# EnvironmentMonitorV2.net
KiCad netlist of a schematic drawn in EAGLE
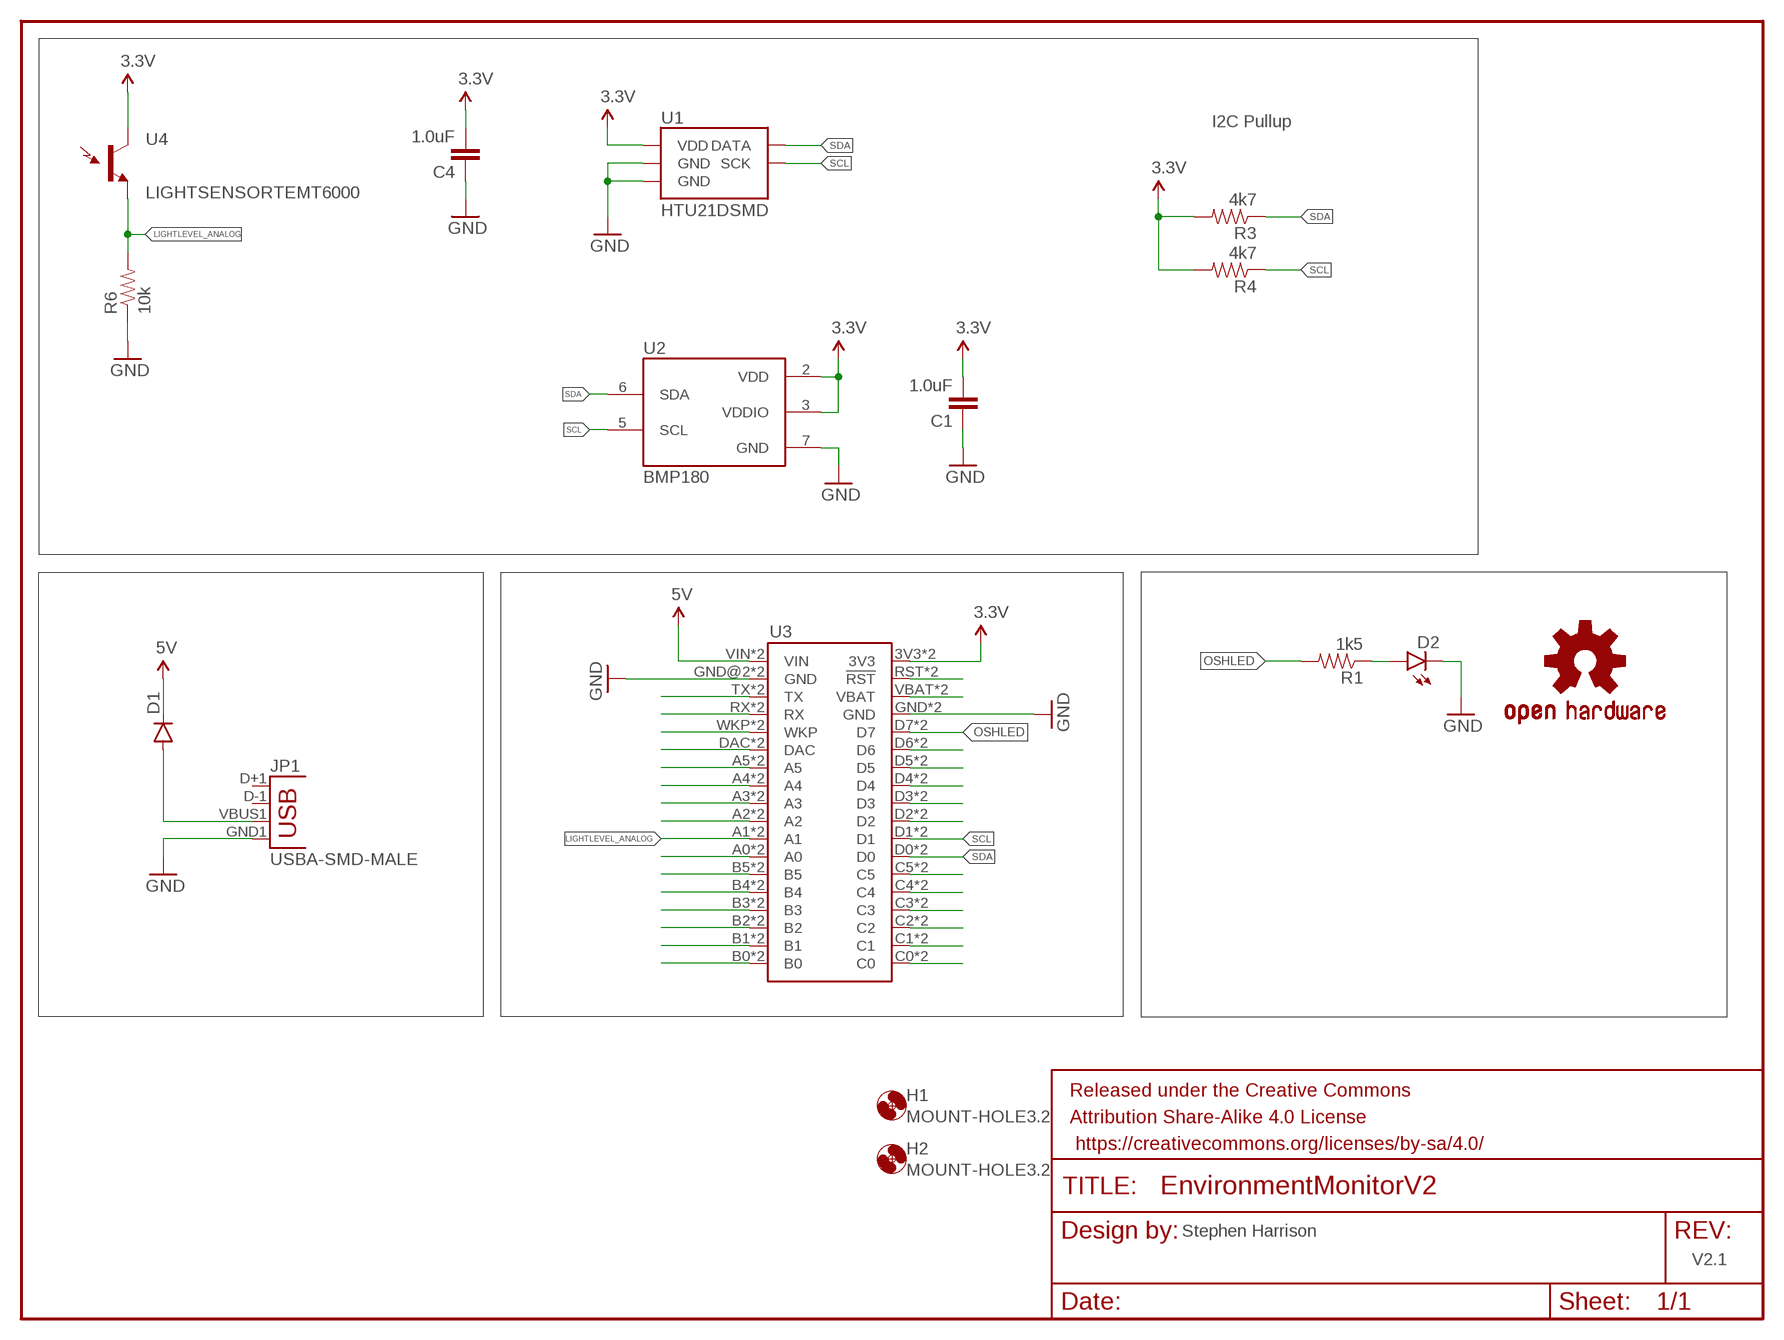
[diagram p0: schematic, sheet 1]

(export (version "E")
  (design (tool "Eeschema 10.0.6"))
  (components
    (comp (ref "C1")
      (value "1.0uF")
      (footprint "eagle-import:0805-CAP")
      (libsource (lib "eagle-import") (part "1.0UF-25V-+80/-20(0805){dblquote}"))
    )
    (comp (ref "C4")
      (value "1.0uF")
      (footprint "eagle-import:0805-CAP")
      (libsource (lib "eagle-import") (part "1.0UF-25V-+80/-20(0805){dblquote}"))
    )
    (comp (ref "D1")
      (value "DIODESMA")
      (footprint "eagle-import:SMA-DIODE")
      (libsource (lib "eagle-import") (part "DIODESMA"))
    )
    (comp (ref "D2")
      (value "LED1206-BOTTOM")
      (footprint "eagle-import:LED-1206-BOTTOM")
      (libsource (lib "eagle-import") (part "LED1206-BOTTOM"))
    )
    (comp (ref "FRAME1")
      (value "FRAME-LETTER")
      (footprint "eagle-import:CREATIVE_COMMONS")
      (libsource (lib "eagle-import") (part "FRAME-LETTER"))
    )
    (comp (ref "H1")
      (value "MOUNT-HOLE3.2")
      (footprint "eagle-import:3,2")
      (libsource (lib "eagle-import") (part "MOUNT-HOLE3.2"))
    )
    (comp (ref "H2")
      (value "MOUNT-HOLE3.2")
      (footprint "eagle-import:3,2")
      (libsource (lib "eagle-import") (part "MOUNT-HOLE3.2"))
    )
    (comp (ref "JP1")
      (value "USBA-SMD-MALE")
      (footprint "eagle-import:USB-A-SMT-MALE")
      (libsource (lib "eagle-import") (part "USBA-SMD-MALE"))
    )
    (comp (ref "LOGO1")
      (value "OSHW-LOGOM")
      (footprint "eagle-import:OSHW-LOGO-M")
      (libsource (lib "eagle-import") (part "OSHW-LOGOM"))
    )
    (comp (ref "R1")
      (value "1k5")
      (footprint "eagle-import:0805")
      (libsource (lib "eagle-import") (part "RESISTOR0805-RES"))
    )
    (comp (ref "R3")
      (value "4k7")
      (footprint "eagle-import:0805")
      (libsource (lib "eagle-import") (part "RESISTOR0805-RES"))
    )
    (comp (ref "R4")
      (value "4k7")
      (footprint "eagle-import:0805")
      (libsource (lib "eagle-import") (part "RESISTOR0805-RES"))
    )
    (comp (ref "R6")
      (value "10k")
      (footprint "eagle-import:0805")
      (libsource (lib "eagle-import") (part "RESISTOR0805-RES"))
    )
    (comp (ref "U1")
      (value "HTU21DSMD")
      (footprint "eagle-import:HTU21D")
      (libsource (lib "eagle-import") (part "HTU21DSMD"))
    )
    (comp (ref "U2")
      (value "BMP180")
      (footprint "eagle-import:BMP180")
      (libsource (lib "eagle-import") (part "BMP180"))
    )
    (comp (ref "U3")
      (value "ELECTRONDUALNAMED")
      (footprint "eagle-import:ELECTRON_SIMPLE_SILK_NAMES_DUAL")
      (libsource (lib "eagle-import") (part "ELECTRONDUALNAMED"))
    )
    (comp (ref "U4")
      (value "LIGHTSENSORTEMT6000")
      (footprint "eagle-import:TEMT6000-SEN")
      (libsource (lib "eagle-import") (part "LIGHTSENSORTEMT6000"))
    )
  )
  (nets
    (net (code "1") (name "3.3V") (class "Default")
      (node (ref "C1") (pin "2") (pinfunction "2_2") (pintype "passive"))
      (node (ref "C4") (pin "2") (pinfunction "2_2") (pintype "passive"))
      (node (ref "R3") (pin "2") (pinfunction "2_2") (pintype "passive"))
      (node (ref "R4") (pin "2") (pinfunction "2_2") (pintype "passive"))
      (node (ref "U1") (pin "VDD") (pinfunction "VDD_VDD") (pintype "power_in"))
      (node (ref "U2") (pin "2") (pinfunction "VDD_2") (pintype "power_in"))
      (node (ref "U2") (pin "3") (pinfunction "VDDIO_3") (pintype "power_in"))
      (node (ref "U3") (pin "3V3") (pinfunction "3V3_3V3") (pintype "power_in"))
      (node (ref "U3") (pin "3V3_1") (pinfunction "3V3_3V3_1") (pintype "power_in"))
      (node (ref "U4") (pin "COLLECTOR") (pinfunction "C1_COLLECTOR") (pintype "passive"))
    )
    (net (code "2") (name "5V") (class "Default")
      (node (ref "D1") (pin "C") (pinfunction "C_C") (pintype "passive"))
      (node (ref "U3") (pin "VIN") (pinfunction "VIN_VIN") (pintype "power_in"))
      (node (ref "U3") (pin "VIN_1B") (pinfunction "VIN_VIN_1B") (pintype "power_in"))
    )
    (net (code "3") (name "GND") (class "Default")
      (node (ref "C1") (pin "1") (pinfunction "1_1") (pintype "passive"))
      (node (ref "C4") (pin "1") (pinfunction "1_1") (pintype "passive"))
      (node (ref "D2") (pin "C") (pinfunction "C_C") (pintype "passive"))
      (node (ref "JP1") (pin "GND1") (pinfunction "GND_GND1") (pintype "bidirectional"))
      (node (ref "R6") (pin "1") (pinfunction "1_1") (pintype "passive"))
      (node (ref "U1") (pin "7") (pinfunction "GND_7") (pintype "power_in"))
      (node (ref "U1") (pin "GND") (pinfunction "GND_GND") (pintype "power_in"))
      (node (ref "U2") (pin "7") (pinfunction "GND_7") (pintype "power_in"))
      (node (ref "U3") (pin "GND") (pinfunction "GND_GND") (pintype "power_in"))
      (node (ref "U3") (pin "GND@2") (pinfunction "GND_GND@2") (pintype "power_in"))
      (node (ref "U3") (pin "GND_1") (pinfunction "GND_GND_1") (pintype "power_in"))
      (node (ref "U3") (pin "GND_1B") (pinfunction "GND_GND_1B") (pintype "power_in"))
    )
    (net (code "4") (name "LIGHTLEVEL_ANALOG") (class "Default")
      (node (ref "R6") (pin "2") (pinfunction "2_2") (pintype "passive"))
      (node (ref "U3") (pin "A1") (pinfunction "A1_A1") (pintype "bidirectional"))
      (node (ref "U3") (pin "A1_1") (pinfunction "A1_A1_1") (pintype "bidirectional"))
      (node (ref "U4") (pin "EMITTER") (pinfunction "E1_EMITTER") (pintype "passive"))
    )
    (net (code "5") (name "Net-(D2-PadA)") (class "Default")
      (node (ref "D2") (pin "A") (pinfunction "A_A") (pintype "passive"))
      (node (ref "R1") (pin "1") (pinfunction "1_1") (pintype "passive"))
    )
    (net (code "6") (name "Net-(JP1-VBUS)") (class "Default")
      (node (ref "D1") (pin "A") (pinfunction "A_A") (pintype "passive"))
      (node (ref "JP1") (pin "VBUS1") (pinfunction "VBUS_VBUS1") (pintype "bidirectional"))
    )
    (net (code "7") (name "Net-(U3-A0-PadA0_1)") (class "Default")
      (node (ref "U3") (pin "A0") (pinfunction "A0_A0") (pintype "bidirectional"))
      (node (ref "U3") (pin "A0_1") (pinfunction "A0_A0_1") (pintype "bidirectional"))
    )
    (net (code "8") (name "Net-(U3-A2-PadA2_1)") (class "Default")
      (node (ref "U3") (pin "A2") (pinfunction "A2_A2") (pintype "bidirectional"))
      (node (ref "U3") (pin "A2_1") (pinfunction "A2_A2_1") (pintype "bidirectional"))
    )
    (net (code "9") (name "Net-(U3-A3-PadA3_1)") (class "Default")
      (node (ref "U3") (pin "A3") (pinfunction "A3_A3") (pintype "bidirectional"))
      (node (ref "U3") (pin "A3_1") (pinfunction "A3_A3_1") (pintype "bidirectional"))
    )
    (net (code "10") (name "Net-(U3-A4-PadA4_1)") (class "Default")
      (node (ref "U3") (pin "A4") (pinfunction "A4_A4") (pintype "bidirectional"))
      (node (ref "U3") (pin "A4_1") (pinfunction "A4_A4_1") (pintype "bidirectional"))
    )
    (net (code "11") (name "Net-(U3-A5-PadA5_1)") (class "Default")
      (node (ref "U3") (pin "A5") (pinfunction "A5_A5") (pintype "bidirectional"))
      (node (ref "U3") (pin "A5_1") (pinfunction "A5_A5_1") (pintype "bidirectional"))
    )
    (net (code "12") (name "Net-(U3-B0-PadB0_1)") (class "Default")
      (node (ref "U3") (pin "B0") (pinfunction "B0_B0") (pintype "bidirectional"))
      (node (ref "U3") (pin "B0_1") (pinfunction "B0_B0_1") (pintype "bidirectional"))
    )
    (net (code "13") (name "Net-(U3-B1-PadB1_1)") (class "Default")
      (node (ref "U3") (pin "B1") (pinfunction "B1_B1") (pintype "bidirectional"))
      (node (ref "U3") (pin "B1_1") (pinfunction "B1_B1_1") (pintype "bidirectional"))
    )
    (net (code "14") (name "Net-(U3-B2-PadB2_1)") (class "Default")
      (node (ref "U3") (pin "B2") (pinfunction "B2_B2") (pintype "bidirectional"))
      (node (ref "U3") (pin "B2_1") (pinfunction "B2_B2_1") (pintype "bidirectional"))
    )
    (net (code "15") (name "Net-(U3-B3-PadB3_1)") (class "Default")
      (node (ref "U3") (pin "B3") (pinfunction "B3_B3") (pintype "bidirectional"))
      (node (ref "U3") (pin "B3_1") (pinfunction "B3_B3_1") (pintype "bidirectional"))
    )
    (net (code "16") (name "Net-(U3-B4-PadB4_1)") (class "Default")
      (node (ref "U3") (pin "B4") (pinfunction "B4_B4") (pintype "bidirectional"))
      (node (ref "U3") (pin "B4_1") (pinfunction "B4_B4_1") (pintype "bidirectional"))
    )
    (net (code "17") (name "Net-(U3-B5-PadB5_1)") (class "Default")
      (node (ref "U3") (pin "B5") (pinfunction "B5_B5") (pintype "bidirectional"))
      (node (ref "U3") (pin "B5_1") (pinfunction "B5_B5_1") (pintype "bidirectional"))
    )
    (net (code "18") (name "Net-(U3-C0-PadC0_1)") (class "Default")
      (node (ref "U3") (pin "C0") (pinfunction "C0_C0") (pintype "bidirectional"))
      (node (ref "U3") (pin "C0_1") (pinfunction "C0_C0_1") (pintype "bidirectional"))
    )
    (net (code "19") (name "Net-(U3-C1-PadC1_1)") (class "Default")
      (node (ref "U3") (pin "C1") (pinfunction "C1_C1") (pintype "bidirectional"))
      (node (ref "U3") (pin "C1_1") (pinfunction "C1_C1_1") (pintype "bidirectional"))
    )
    (net (code "20") (name "Net-(U3-C2-PadC2_1)") (class "Default")
      (node (ref "U3") (pin "C2") (pinfunction "C2_C2") (pintype "bidirectional"))
      (node (ref "U3") (pin "C2_1") (pinfunction "C2_C2_1") (pintype "bidirectional"))
    )
    (net (code "21") (name "Net-(U3-C3-PadC3_1)") (class "Default")
      (node (ref "U3") (pin "C3") (pinfunction "C3_C3") (pintype "bidirectional"))
      (node (ref "U3") (pin "C3_1") (pinfunction "C3_C3_1") (pintype "bidirectional"))
    )
    (net (code "22") (name "Net-(U3-C4-PadC4_1)") (class "Default")
      (node (ref "U3") (pin "C4") (pinfunction "C4_C4") (pintype "bidirectional"))
      (node (ref "U3") (pin "C4_1") (pinfunction "C4_C4_1") (pintype "bidirectional"))
    )
    (net (code "23") (name "Net-(U3-C5-PadC5_1)") (class "Default")
      (node (ref "U3") (pin "C5") (pinfunction "C5_C5") (pintype "bidirectional"))
      (node (ref "U3") (pin "C5_1") (pinfunction "C5_C5_1") (pintype "bidirectional"))
    )
    (net (code "24") (name "Net-(U3-D2-PadD2_1)") (class "Default")
      (node (ref "U3") (pin "D2") (pinfunction "D2_D2") (pintype "bidirectional"))
      (node (ref "U3") (pin "D2_1") (pinfunction "D2_D2_1") (pintype "bidirectional"))
    )
    (net (code "25") (name "Net-(U3-D3-PadD3_1)") (class "Default")
      (node (ref "U3") (pin "D3") (pinfunction "D3_D3") (pintype "bidirectional"))
      (node (ref "U3") (pin "D3_1") (pinfunction "D3_D3_1") (pintype "bidirectional"))
    )
    (net (code "26") (name "Net-(U3-D4-PadD4_1)") (class "Default")
      (node (ref "U3") (pin "D4") (pinfunction "D4_D4") (pintype "bidirectional"))
      (node (ref "U3") (pin "D4_1") (pinfunction "D4_D4_1") (pintype "bidirectional"))
    )
    (net (code "27") (name "Net-(U3-D5-PadD5_1)") (class "Default")
      (node (ref "U3") (pin "D5") (pinfunction "D5_D5") (pintype "bidirectional"))
      (node (ref "U3") (pin "D5_1") (pinfunction "D5_D5_1") (pintype "bidirectional"))
    )
    (net (code "28") (name "Net-(U3-D6-PadD6_1)") (class "Default")
      (node (ref "U3") (pin "D6") (pinfunction "D6_D6") (pintype "bidirectional"))
      (node (ref "U3") (pin "D6_1") (pinfunction "D6_D6_1") (pintype "bidirectional"))
    )
    (net (code "29") (name "Net-(U3-DAC-PadDAC_1)") (class "Default")
      (node (ref "U3") (pin "DAC") (pinfunction "DAC_DAC") (pintype "bidirectional"))
      (node (ref "U3") (pin "DAC_1") (pinfunction "DAC_DAC_1") (pintype "bidirectional"))
    )
    (net (code "30") (name "Net-(U3-PadRX)") (class "Default")
      (node (ref "U3") (pin "RX") (pinfunction "RX_RX") (pintype "bidirectional"))
      (node (ref "U3") (pin "RX_1") (pinfunction "RX_RX_1") (pintype "bidirectional"))
    )
    (net (code "31") (name "Net-(U3-PadTX)") (class "Default")
      (node (ref "U3") (pin "TX") (pinfunction "TX_TX") (pintype "bidirectional"))
      (node (ref "U3") (pin "TX_1") (pinfunction "TX_TX_1") (pintype "bidirectional"))
    )
    (net (code "32") (name "Net-(U3-PadVBAT)") (class "Default")
      (node (ref "U3") (pin "VBAT") (pinfunction "VBAT_VBAT") (pintype "passive"))
      (node (ref "U3") (pin "VBATT_1") (pinfunction "VBAT_VBATT_1") (pintype "passive"))
    )
    (net (code "33") (name "Net-(U3-PadWKP)") (class "Default")
      (node (ref "U3") (pin "WKP") (pinfunction "WKP_WKP") (pintype "bidirectional"))
      (node (ref "U3") (pin "WKP_1") (pinfunction "WKP_WKP_1") (pintype "bidirectional"))
    )
    (net (code "34") (name "Net-(U3-~{RST}-PadRST)") (class "Default")
      (node (ref "U3") (pin "RST") (pinfunction "~{RST}_RST") (pintype "bidirectional"))
      (node (ref "U3") (pin "RST_1") (pinfunction "~{RST}_RST_1") (pintype "bidirectional"))
    )
    (net (code "35") (name "OSHLED") (class "Default")
      (node (ref "R1") (pin "2") (pinfunction "2_2") (pintype "passive"))
      (node (ref "U3") (pin "D7") (pinfunction "D7_D7") (pintype "bidirectional"))
      (node (ref "U3") (pin "D7_1") (pinfunction "D7_D7_1") (pintype "bidirectional"))
    )
    (net (code "36") (name "SCL") (class "Default")
      (node (ref "R4") (pin "1") (pinfunction "1_1") (pintype "passive"))
      (node (ref "U1") (pin "SCK") (pinfunction "SCK_SCK") (pintype "input"))
      (node (ref "U2") (pin "5") (pinfunction "SCL_5") (pintype "input"))
      (node (ref "U3") (pin "D1") (pinfunction "D1_D1") (pintype "bidirectional"))
      (node (ref "U3") (pin "D1_1") (pinfunction "D1_D1_1") (pintype "bidirectional"))
    )
    (net (code "37") (name "SDA") (class "Default")
      (node (ref "R3") (pin "1") (pinfunction "1_1") (pintype "passive"))
      (node (ref "U1") (pin "DATA") (pinfunction "DATA_DATA") (pintype "bidirectional"))
      (node (ref "U2") (pin "6") (pinfunction "SDA_6") (pintype "bidirectional"))
      (node (ref "U3") (pin "D0") (pinfunction "D0_D0") (pintype "bidirectional"))
      (node (ref "U3") (pin "D0_1") (pinfunction "D0_D0_1") (pintype "bidirectional"))
    )
    (net (code "38") (name "unconnected-(JP1-D+-PadD+1)") (class "Default")
      (node (ref "JP1") (pin "D+1") (pinfunction "D+_D+1") (pintype "bidirectional"))
    )
    (net (code "39") (name "unconnected-(JP1-D--PadD-1)") (class "Default")
      (node (ref "JP1") (pin "D-1") (pinfunction "D-_D-1") (pintype "bidirectional"))
    )
  )
)
